# sparrow-though-jack-var.net
KiCad netlist of a schematic drawn in EAGLE
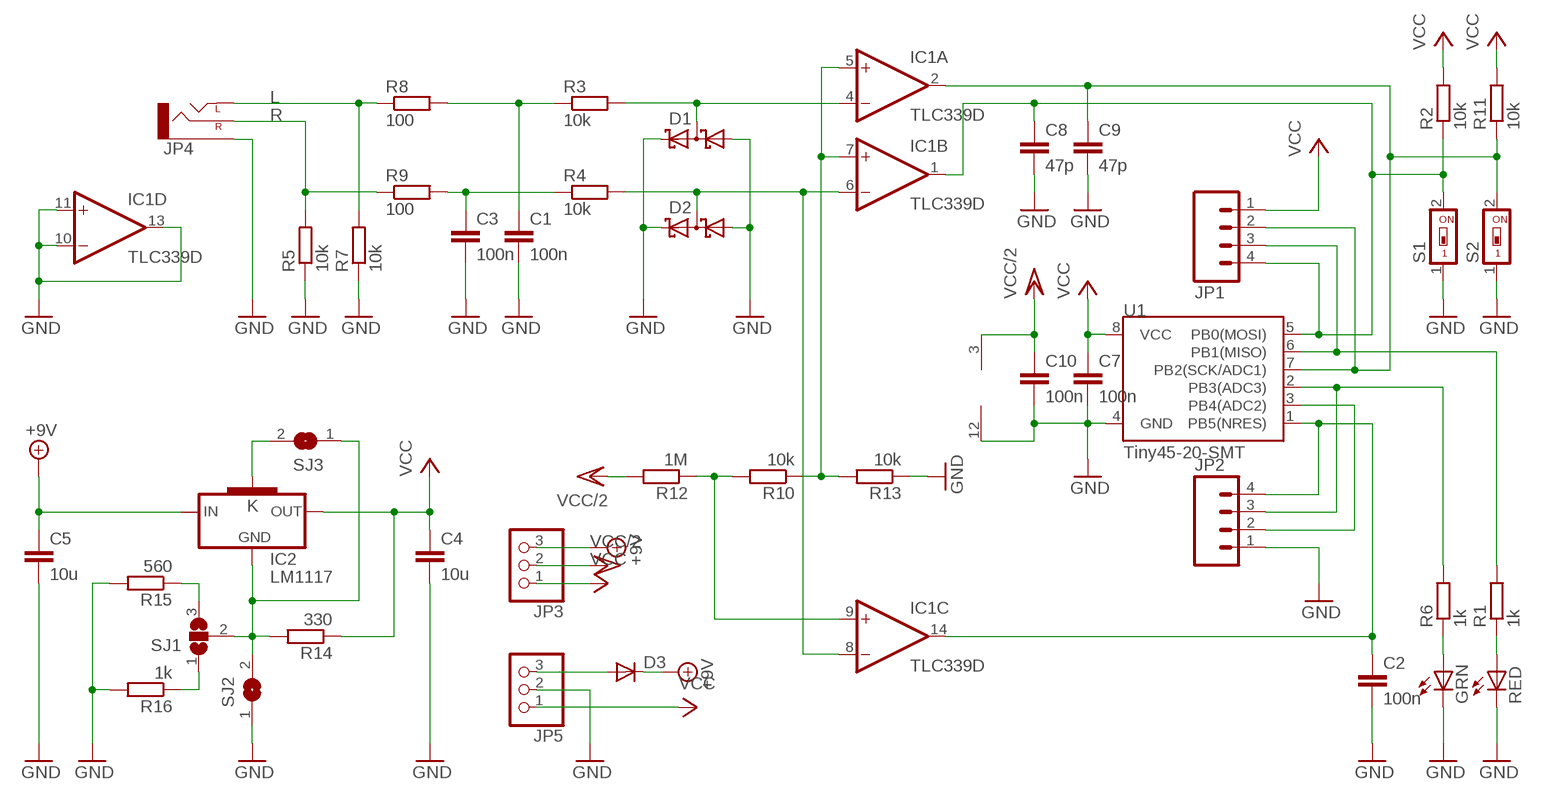
[diagram p0: schematic, sheet 1]

(export (version "E")
  (design (tool "Eeschema 10.0.6"))
  (components
    (comp (ref "C1")
      (value "100n")
      (footprint "eagle-import:C0805K")
      (libsource (lib "eagle-import") (part "C-EUC0805K"))
    )
    (comp (ref "C2")
      (value "100n")
      (footprint "eagle-import:C0805K")
      (libsource (lib "eagle-import") (part "C-EUC0805K"))
    )
    (comp (ref "C3")
      (value "100n")
      (footprint "eagle-import:C0805K")
      (libsource (lib "eagle-import") (part "C-EUC0805K"))
    )
    (comp (ref "C4")
      (value "10u")
      (footprint "eagle-import:C0805K")
      (libsource (lib "eagle-import") (part "C-EUC0805K"))
    )
    (comp (ref "C5")
      (value "10u")
      (footprint "eagle-import:C0805K")
      (libsource (lib "eagle-import") (part "C-EUC0805K"))
    )
    (comp (ref "C7")
      (value "100n")
      (footprint "eagle-import:C0805K")
      (libsource (lib "eagle-import") (part "C-EUC0805K"))
    )
    (comp (ref "C8")
      (value "47p")
      (footprint "eagle-import:C0805K")
      (libsource (lib "eagle-import") (part "C-EUC0805K"))
    )
    (comp (ref "C9")
      (value "47p")
      (footprint "eagle-import:C0805K")
      (libsource (lib "eagle-import") (part "C-EUC0805K"))
    )
    (comp (ref "C10")
      (value "100n")
      (footprint "eagle-import:C0805K")
      (libsource (lib "eagle-import") (part "C-EUC0805K"))
    )
    (comp (ref "D1")
      (value "BAT54S")
      (footprint "eagle-import:SOT23")
      (libsource (lib "eagle-import") (part "BAT54S"))
    )
    (comp (ref "D2")
      (value "BAT54S")
      (footprint "eagle-import:SOT23")
      (libsource (lib "eagle-import") (part "BAT54S"))
    )
    (comp (ref "D3")
      (value "DIODE-MINIMELF")
      (footprint "eagle-import:MINIMELF")
      (libsource (lib "eagle-import") (part "DIODE-MINIMELF"))
    )
    (comp (ref "GRN")
      (value "LEDCHIP-LED0805")
      (footprint "eagle-import:CHIP-LED0805")
      (libsource (lib "eagle-import") (part "LEDCHIP-LED0805"))
    )
    (comp (ref "IC1")
      (value "TLC339D")
      (footprint "eagle-import:SO14")
      (libsource (lib "eagle-import") (part "TLC339D"))
    )
    (comp (ref "IC2")
      (value "LM1117")
      (footprint "eagle-import:SOT223")
      (libsource (lib "eagle-import") (part "LD1117S50"))
    )
    (comp (ref "JP1")
      (value "M04PTH")
      (footprint "eagle-import:1X04")
      (libsource (lib "eagle-import") (part "M04PTH"))
    )
    (comp (ref "JP2")
      (value "M04PTH")
      (footprint "eagle-import:1X04")
      (libsource (lib "eagle-import") (part "M04PTH"))
    )
    (comp (ref "JP3")
      (value "PINHD-1X3")
      (footprint "eagle-import:1X03")
      (libsource (lib "eagle-import") (part "PINHD-1X3"))
    )
    (comp (ref "JP4")
      (value "AUDIO-JACKPIN-HOLES")
      (footprint "eagle-import:AUDIO-JACK-HOLES")
      (libsource (lib "eagle-import") (part "AUDIO-JACKPIN-HOLES"))
    )
    (comp (ref "JP5")
      (value "PINHD-1X3")
      (footprint "eagle-import:1X03")
      (libsource (lib "eagle-import") (part "PINHD-1X3"))
    )
    (comp (ref "R1")
      (value "1k")
      (footprint "eagle-import:M0805")
      (libsource (lib "eagle-import") (part "R-EU_M0805"))
    )
    (comp (ref "R2")
      (value "10k")
      (footprint "eagle-import:M0805")
      (libsource (lib "eagle-import") (part "R-EU_M0805"))
    )
    (comp (ref "R3")
      (value "10k")
      (footprint "eagle-import:M0805")
      (libsource (lib "eagle-import") (part "R-EU_M0805"))
    )
    (comp (ref "R4")
      (value "10k")
      (footprint "eagle-import:M0805")
      (libsource (lib "eagle-import") (part "R-EU_M0805"))
    )
    (comp (ref "R5")
      (value "10k")
      (footprint "eagle-import:M0805")
      (libsource (lib "eagle-import") (part "R-EU_M0805"))
    )
    (comp (ref "R6")
      (value "1k")
      (footprint "eagle-import:M0805")
      (libsource (lib "eagle-import") (part "R-EU_M0805"))
    )
    (comp (ref "R7")
      (value "10k")
      (footprint "eagle-import:M0805")
      (libsource (lib "eagle-import") (part "R-EU_M0805"))
    )
    (comp (ref "R8")
      (value "100")
      (footprint "eagle-import:M0805")
      (libsource (lib "eagle-import") (part "R-EU_M0805"))
    )
    (comp (ref "R9")
      (value "100")
      (footprint "eagle-import:M0805")
      (libsource (lib "eagle-import") (part "R-EU_M0805"))
    )
    (comp (ref "R10")
      (value "10k")
      (footprint "eagle-import:M0805")
      (libsource (lib "eagle-import") (part "R-EU_M0805"))
    )
    (comp (ref "R11")
      (value "10k")
      (footprint "eagle-import:M0805")
      (libsource (lib "eagle-import") (part "R-EU_M0805"))
    )
    (comp (ref "R12")
      (value "1M")
      (footprint "eagle-import:M0805")
      (libsource (lib "eagle-import") (part "R-EU_M0805"))
    )
    (comp (ref "R13")
      (value "10k")
      (footprint "eagle-import:M0805")
      (libsource (lib "eagle-import") (part "R-EU_M0805"))
    )
    (comp (ref "R14")
      (value "330")
      (footprint "eagle-import:M0805")
      (libsource (lib "eagle-import") (part "R-EU_M0805"))
    )
    (comp (ref "R15")
      (value "560")
      (footprint "eagle-import:M0805")
      (libsource (lib "eagle-import") (part "R-EU_M0805"))
    )
    (comp (ref "R16")
      (value "1k")
      (footprint "eagle-import:M0805")
      (libsource (lib "eagle-import") (part "R-EU_M0805"))
    )
    (comp (ref "RED")
      (value "LEDCHIP-LED0805")
      (footprint "eagle-import:CHIP-LED0805")
      (libsource (lib "eagle-import") (part "LEDCHIP-LED0805"))
    )
    (comp (ref "S1")
      (value "SWS001")
      (footprint "eagle-import:SMS-001")
      (libsource (lib "eagle-import") (part "SWS001"))
    )
    (comp (ref "S2")
      (value "SWS001")
      (footprint "eagle-import:SMS-001")
      (libsource (lib "eagle-import") (part "SWS001"))
    )
    (comp (ref "SJ1")
      (value "SJ2W")
      (footprint "eagle-import:SJ_2")
      (libsource (lib "eagle-import") (part "SJ2W"))
    )
    (comp (ref "SJ2") (value "SJ") (footprint "eagle-import:SJ") (libsource (lib "eagle-import") (part "SJ")))
    (comp (ref "SJ3") (value "SJ") (footprint "eagle-import:SJ") (libsource (lib "eagle-import") (part "SJ")))
    (comp (ref "U1")
      (value "Tiny45-20-SMT")
      (footprint "eagle-import:SO08-EIAJ")
      (libsource (lib "eagle-import") (part "ATTINY45TINY45-20-SMT"))
    )
  )
  (nets
    (net (code "1") (name "+9V") (class "Default")
      (node (ref "C5") (pin "1") (pinfunction "1_1") (pintype "passive"))
      (node (ref "D3") (pin "C") (pinfunction "C_C") (pintype "passive"))
      (node (ref "IC2") (pin "3") (pinfunction "IN_3") (pintype "input"))
      (node (ref "JP3") (pin "3") (pinfunction "3_3") (pintype "passive"))
    )
    (net (code "2") (name "/L") (class "Default")
      (node (ref "JP4") (pin "L1-") (pinfunction "LEFT_L1-") (pintype "bidirectional"))
      (node (ref "JP4") (pin "L2-") (pinfunction "LEFT_L2-") (pintype "bidirectional"))
      (node (ref "R7") (pin "2") (pinfunction "2_2") (pintype "passive"))
      (node (ref "R8") (pin "1") (pinfunction "1_1") (pintype "passive"))
    )
    (net (code "3") (name "/R") (class "Default")
      (node (ref "JP4") (pin "R+") (pinfunction "RIGHT_R+") (pintype "bidirectional"))
      (node (ref "R5") (pin "2") (pinfunction "2_2") (pintype "passive"))
      (node (ref "R9") (pin "1") (pinfunction "1_1") (pintype "passive"))
    )
    (net (code "4") (name "GND") (class "Default")
      (node (ref "C1") (pin "2") (pinfunction "2_2") (pintype "passive"))
      (node (ref "C10") (pin "2") (pinfunction "2_2") (pintype "passive"))
      (node (ref "C2") (pin "2") (pinfunction "2_2") (pintype "passive"))
      (node (ref "C3") (pin "2") (pinfunction "2_2") (pintype "passive"))
      (node (ref "C4") (pin "2") (pinfunction "2_2") (pintype "passive"))
      (node (ref "C5") (pin "2") (pinfunction "2_2") (pintype "passive"))
      (node (ref "C7") (pin "2") (pinfunction "2_2") (pintype "passive"))
      (node (ref "C8") (pin "2") (pinfunction "2_2") (pintype "passive"))
      (node (ref "C9") (pin "2") (pinfunction "2_2") (pintype "passive"))
      (node (ref "D1") (pin "1") (pinfunction "A1_1") (pintype "passive"))
      (node (ref "D1") (pin "2") (pinfunction "C2_2") (pintype "passive"))
      (node (ref "D2") (pin "1") (pinfunction "A1_1") (pintype "passive"))
      (node (ref "D2") (pin "2") (pinfunction "C2_2") (pintype "passive"))
      (node (ref "GRN") (pin "C") (pinfunction "C_C") (pintype "passive"))
      (node (ref "IC1") (pin "10") (pinfunction "-IN_10") (pintype "input"))
      (node (ref "IC1") (pin "11") (pinfunction "+IN_11") (pintype "input"))
      (node (ref "IC1") (pin "12") (pinfunction "V-_12") (pintype "power_in"))
      (node (ref "IC1") (pin "13") (pinfunction "OUT_13") (pintype "output"))
      (node (ref "JP2") (pin "1") (pinfunction "1_1") (pintype "passive"))
      (node (ref "JP4") (pin "GND") (pinfunction "SLEEVE_GND") (pintype "bidirectional"))
      (node (ref "JP5") (pin "2") (pinfunction "2_2") (pintype "passive"))
      (node (ref "R13") (pin "1") (pinfunction "1_1") (pintype "passive"))
      (node (ref "R15") (pin "2") (pinfunction "2_2") (pintype "passive"))
      (node (ref "R16") (pin "2") (pinfunction "2_2") (pintype "passive"))
      (node (ref "R5") (pin "1") (pinfunction "1_1") (pintype "passive"))
      (node (ref "R7") (pin "1") (pinfunction "1_1") (pintype "passive"))
      (node (ref "RED") (pin "C") (pinfunction "C_C") (pintype "passive"))
      (node (ref "S1") (pin "1") (pinfunction "1_1") (pintype "passive"))
      (node (ref "S2") (pin "1") (pinfunction "1_1") (pintype "passive"))
      (node (ref "SJ2") (pin "1") (pinfunction "1_1") (pintype "passive"))
      (node (ref "U1") (pin "4") (pinfunction "GND_4") (pintype "bidirectional"))
    )
    (net (code "5") (name "Net-(C1-Pad1)") (class "Default")
      (node (ref "C1") (pin "1") (pinfunction "1_1") (pintype "passive"))
      (node (ref "R3") (pin "1") (pinfunction "1_1") (pintype "passive"))
      (node (ref "R8") (pin "2") (pinfunction "2_2") (pintype "passive"))
    )
    (net (code "6") (name "Net-(C3-Pad1)") (class "Default")
      (node (ref "C3") (pin "1") (pinfunction "1_1") (pintype "passive"))
      (node (ref "R4") (pin "1") (pinfunction "1_1") (pintype "passive"))
      (node (ref "R9") (pin "2") (pinfunction "2_2") (pintype "passive"))
    )
    (net (code "7") (name "Net-(D1-C1A2)") (class "Default")
      (node (ref "D1") (pin "3") (pinfunction "C1A2_3") (pintype "passive"))
      (node (ref "IC1") (pin "4") (pinfunction "-IN_4") (pintype "input"))
      (node (ref "R3") (pin "2") (pinfunction "2_2") (pintype "passive"))
    )
    (net (code "8") (name "Net-(D2-C1A2)") (class "Default")
      (node (ref "D2") (pin "3") (pinfunction "C1A2_3") (pintype "passive"))
      (node (ref "IC1") (pin "6") (pinfunction "-IN_6") (pintype "input"))
      (node (ref "IC1") (pin "8") (pinfunction "-IN_8") (pintype "input"))
      (node (ref "R4") (pin "2") (pinfunction "2_2") (pintype "passive"))
    )
    (net (code "9") (name "Net-(D3-PadA)") (class "Default")
      (node (ref "D3") (pin "A") (pinfunction "A_A") (pintype "passive"))
      (node (ref "JP5") (pin "3") (pinfunction "3_3") (pintype "passive"))
    )
    (net (code "10") (name "Net-(GRN-PadA)") (class "Default")
      (node (ref "GRN") (pin "A") (pinfunction "A_A") (pintype "passive"))
      (node (ref "R6") (pin "1") (pinfunction "1_1") (pintype "passive"))
    )
    (net (code "11") (name "Net-(IC1A-+IN)") (class "Default")
      (node (ref "IC1") (pin "5") (pinfunction "+IN_5") (pintype "input"))
      (node (ref "IC1") (pin "7") (pinfunction "+IN_7") (pintype "input"))
      (node (ref "R10") (pin "1") (pinfunction "1_1") (pintype "passive"))
      (node (ref "R13") (pin "2") (pinfunction "2_2") (pintype "passive"))
    )
    (net (code "12") (name "Net-(IC1A-OUT)") (class "Default")
      (node (ref "C9") (pin "1") (pinfunction "1_1") (pintype "passive"))
      (node (ref "IC1") (pin "2") (pinfunction "OUT_2") (pintype "output"))
      (node (ref "JP1") (pin "2") (pinfunction "2_2") (pintype "passive"))
      (node (ref "R11") (pin "1") (pinfunction "1_1") (pintype "passive"))
      (node (ref "S2") (pin "2") (pinfunction "2_2") (pintype "passive"))
      (node (ref "U1") (pin "7") (pinfunction "PB2(SCK/ADC1)_7") (pintype "bidirectional"))
    )
    (net (code "13") (name "Net-(IC1B-OUT)") (class "Default")
      (node (ref "C8") (pin "1") (pinfunction "1_1") (pintype "passive"))
      (node (ref "IC1") (pin "1") (pinfunction "OUT_1") (pintype "output"))
      (node (ref "JP1") (pin "4") (pinfunction "4_4") (pintype "passive"))
      (node (ref "R2") (pin "1") (pinfunction "1_1") (pintype "passive"))
      (node (ref "S1") (pin "2") (pinfunction "2_2") (pintype "passive"))
      (node (ref "U1") (pin "5") (pinfunction "PB0(MOSI)_5") (pintype "bidirectional"))
    )
    (net (code "14") (name "Net-(IC1C-+IN)") (class "Default")
      (node (ref "IC1") (pin "9") (pinfunction "+IN_9") (pintype "input"))
      (node (ref "R10") (pin "2") (pinfunction "2_2") (pintype "passive"))
      (node (ref "R12") (pin "1") (pinfunction "1_1") (pintype "passive"))
    )
    (net (code "15") (name "Net-(IC1C-OUT)") (class "Default")
      (node (ref "C2") (pin "1") (pinfunction "1_1") (pintype "passive"))
      (node (ref "IC1") (pin "14") (pinfunction "OUT_14") (pintype "output"))
      (node (ref "JP2") (pin "4") (pinfunction "4_4") (pintype "passive"))
      (node (ref "U1") (pin "1") (pinfunction "PB5(NRES)_1") (pintype "bidirectional"))
    )
    (net (code "16") (name "Net-(IC2-GND)") (class "Default")
      (node (ref "IC2") (pin "1") (pinfunction "GND_1") (pintype "input"))
      (node (ref "R14") (pin "2") (pinfunction "2_2") (pintype "passive"))
      (node (ref "SJ1") (pin "2") (pinfunction "2_2") (pintype "passive"))
      (node (ref "SJ2") (pin "2") (pinfunction "2_2") (pintype "passive"))
      (node (ref "SJ3") (pin "1") (pinfunction "1_1") (pintype "passive"))
    )
    (net (code "17") (name "Net-(IC2-K)") (class "Default")
      (node (ref "IC2") (pin "4") (pinfunction "K_4") (pintype "passive"))
      (node (ref "SJ3") (pin "2") (pinfunction "2_2") (pintype "passive"))
    )
    (net (code "18") (name "Net-(R1-Pad1)") (class "Default")
      (node (ref "R1") (pin "1") (pinfunction "1_1") (pintype "passive"))
      (node (ref "RED") (pin "A") (pinfunction "A_A") (pintype "passive"))
    )
    (net (code "19") (name "Net-(R15-Pad1)") (class "Default")
      (node (ref "R15") (pin "1") (pinfunction "1_1") (pintype "passive"))
      (node (ref "SJ1") (pin "3") (pinfunction "3_3") (pintype "passive"))
    )
    (net (code "20") (name "Net-(R16-Pad1)") (class "Default")
      (node (ref "R16") (pin "1") (pinfunction "1_1") (pintype "passive"))
      (node (ref "SJ1") (pin "1") (pinfunction "1_1") (pintype "passive"))
    )
    (net (code "21") (name "Net-(U1-PB1(MISO))") (class "Default")
      (node (ref "JP1") (pin "3") (pinfunction "3_3") (pintype "passive"))
      (node (ref "R1") (pin "2") (pinfunction "2_2") (pintype "passive"))
      (node (ref "U1") (pin "6") (pinfunction "PB1(MISO)_6") (pintype "bidirectional"))
    )
    (net (code "22") (name "Net-(U1-PB3(ADC3))") (class "Default")
      (node (ref "JP2") (pin "3") (pinfunction "3_3") (pintype "passive"))
      (node (ref "R6") (pin "2") (pinfunction "2_2") (pintype "passive"))
      (node (ref "U1") (pin "2") (pinfunction "PB3(ADC3)_2") (pintype "bidirectional"))
    )
    (net (code "23") (name "Net-(U1-PB4(ADC2))") (class "Default")
      (node (ref "JP2") (pin "2") (pinfunction "2_2") (pintype "passive"))
      (node (ref "U1") (pin "3") (pinfunction "PB4(ADC2)_3") (pintype "bidirectional"))
    )
    (net (code "24") (name "VCC") (class "Default")
      (node (ref "C4") (pin "1") (pinfunction "1_1") (pintype "passive"))
      (node (ref "C7") (pin "1") (pinfunction "1_1") (pintype "passive"))
      (node (ref "IC2") (pin "2") (pinfunction "OUT_2") (pintype "passive"))
      (node (ref "JP1") (pin "1") (pinfunction "1_1") (pintype "passive"))
      (node (ref "JP3") (pin "1") (pinfunction "1_1") (pintype "passive"))
      (node (ref "JP5") (pin "1") (pinfunction "1_1") (pintype "passive"))
      (node (ref "R11") (pin "2") (pinfunction "2_2") (pintype "passive"))
      (node (ref "R14") (pin "1") (pinfunction "1_1") (pintype "passive"))
      (node (ref "R2") (pin "2") (pinfunction "2_2") (pintype "passive"))
      (node (ref "U1") (pin "8") (pinfunction "VCC_8") (pintype "bidirectional"))
    )
    (net (code "25") (name "VCC{slash}2") (class "Default")
      (node (ref "C10") (pin "1") (pinfunction "1_1") (pintype "passive"))
      (node (ref "IC1") (pin "3") (pinfunction "V+_3") (pintype "power_in"))
      (node (ref "JP3") (pin "2") (pinfunction "2_2") (pintype "passive"))
      (node (ref "R12") (pin "2") (pinfunction "2_2") (pintype "passive"))
    )
  )
)
